# can_skin.net
KiCad netlist of a schematic drawn in EAGLE
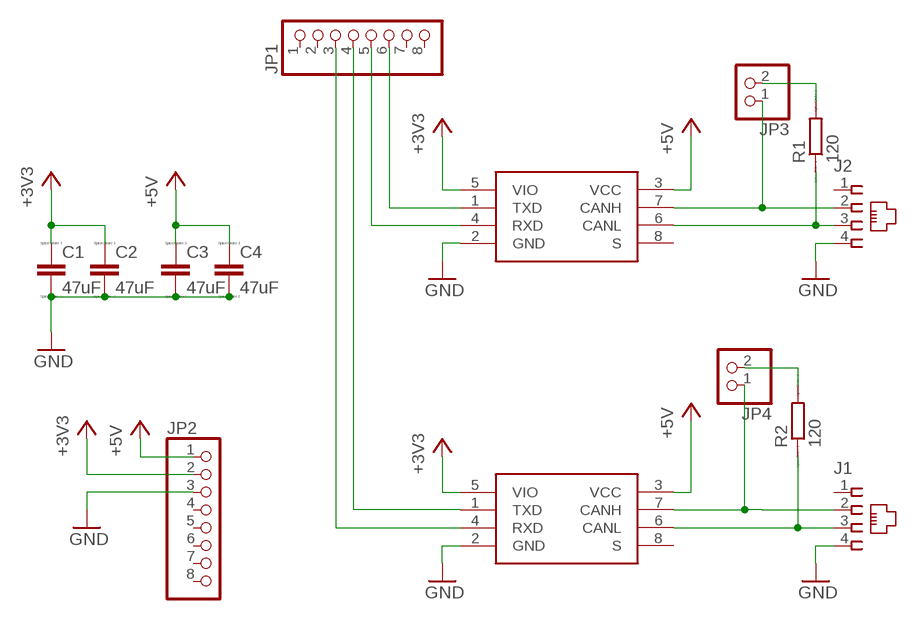
[diagram p0: schematic, sheet 1]

(export (version "E")
  (design (tool "Eeschema 10.0.6"))
  (components
    (comp (ref "C1")
      (value "47uF")
      (footprint "eagle-import:C3216")
      (libsource (lib "eagle-import") (part "C-EUC3216"))
    )
    (comp (ref "C2")
      (value "47uF")
      (footprint "eagle-import:C3216")
      (libsource (lib "eagle-import") (part "C-EUC3216"))
    )
    (comp (ref "C3")
      (value "47uF")
      (footprint "eagle-import:C3216")
      (libsource (lib "eagle-import") (part "C-EUC3216"))
    )
    (comp (ref "C4")
      (value "47uF")
      (footprint "eagle-import:C3216")
      (libsource (lib "eagle-import") (part "C-EUC3216"))
    )
    (comp (ref "J1")
      (value "215875-3")
      (footprint "eagle-import:215875-3")
      (libsource (lib "eagle-import") (part "215875-3"))
    )
    (comp (ref "J2")
      (value "215875-3")
      (footprint "eagle-import:215875-3")
      (libsource (lib "eagle-import") (part "215875-3"))
    )
    (comp (ref "JP1")
      (value "PINHD-1X8")
      (footprint "eagle-import:1X08")
      (libsource (lib "eagle-import") (part "PINHD-1X8"))
    )
    (comp (ref "JP2")
      (value "PINHD-1X8")
      (footprint "eagle-import:1X08")
      (libsource (lib "eagle-import") (part "PINHD-1X8"))
    )
    (comp (ref "JP3")
      (value "PINHD-1X2")
      (footprint "eagle-import:1X02")
      (libsource (lib "eagle-import") (part "PINHD-1X2"))
    )
    (comp (ref "JP4")
      (value "PINHD-1X2")
      (footprint "eagle-import:1X02")
      (libsource (lib "eagle-import") (part "PINHD-1X2"))
    )
    (comp (ref "R1")
      (value "120")
      (footprint "eagle-import:M3216")
      (libsource (lib "eagle-import") (part "R-EU_M3216"))
    )
    (comp (ref "R2")
      (value "120")
      (footprint "eagle-import:M3216")
      (libsource (lib "eagle-import") (part "R-EU_M3216"))
    )
    (comp (ref "U1")
      (value "TJA1051T/3")
      (footprint "eagle-import:SOIC127P600X175-8N")
      (libsource (lib "eagle-import") (part "TJA1051T/3"))
    )
    (comp (ref "U2")
      (value "TJA1051T/3")
      (footprint "eagle-import:SOIC127P600X175-8N")
      (libsource (lib "eagle-import") (part "TJA1051T/3"))
    )
  )
  (nets
    (net (code "1") (name "+3V3") (class "Default")
      (node (ref "C1") (pin "1") (pinfunction "1_1") (pintype "passive"))
      (node (ref "C2") (pin "1") (pinfunction "1_1") (pintype "passive"))
      (node (ref "JP2") (pin "2") (pinfunction "2_2") (pintype "passive"))
      (node (ref "U1") (pin "5") (pinfunction "VIO_5") (pintype "bidirectional"))
      (node (ref "U2") (pin "5") (pinfunction "VIO_5") (pintype "bidirectional"))
    )
    (net (code "2") (name "+5V") (class "Default")
      (node (ref "C3") (pin "1") (pinfunction "1_1") (pintype "passive"))
      (node (ref "C4") (pin "1") (pinfunction "1_1") (pintype "passive"))
      (node (ref "JP2") (pin "1") (pinfunction "1_1") (pintype "passive"))
      (node (ref "U1") (pin "3") (pinfunction "VCC_3") (pintype "bidirectional"))
      (node (ref "U2") (pin "3") (pinfunction "VCC_3") (pintype "bidirectional"))
    )
    (net (code "3") (name "GND") (class "Default")
      (node (ref "C1") (pin "2") (pinfunction "2_2") (pintype "passive"))
      (node (ref "C2") (pin "2") (pinfunction "2_2") (pintype "passive"))
      (node (ref "C3") (pin "2") (pinfunction "2_2") (pintype "passive"))
      (node (ref "C4") (pin "2") (pinfunction "2_2") (pintype "passive"))
      (node (ref "J1") (pin "4") (pinfunction "4_4") (pintype "passive"))
      (node (ref "J2") (pin "4") (pinfunction "4_4") (pintype "passive"))
      (node (ref "JP2") (pin "3") (pinfunction "3_3") (pintype "passive"))
      (node (ref "U1") (pin "2") (pinfunction "GND_2") (pintype "bidirectional"))
      (node (ref "U2") (pin "2") (pinfunction "GND_2") (pintype "bidirectional"))
    )
    (net (code "4") (name "Net-(JP3-Pad2)") (class "Default")
      (node (ref "JP3") (pin "2") (pinfunction "2_2") (pintype "passive"))
      (node (ref "R1") (pin "2") (pinfunction "2_2") (pintype "passive"))
    )
    (net (code "5") (name "Net-(JP4-Pad2)") (class "Default")
      (node (ref "JP4") (pin "2") (pinfunction "2_2") (pintype "passive"))
      (node (ref "R2") (pin "2") (pinfunction "2_2") (pintype "passive"))
    )
    (net (code "6") (name "Net-(U1-CANH)") (class "Default")
      (node (ref "J1") (pin "2") (pinfunction "2_2") (pintype "passive"))
      (node (ref "JP4") (pin "1") (pinfunction "1_1") (pintype "passive"))
      (node (ref "U1") (pin "7") (pinfunction "CANH_7") (pintype "bidirectional"))
    )
    (net (code "7") (name "Net-(U1-CANL)") (class "Default")
      (node (ref "J1") (pin "3") (pinfunction "3_3") (pintype "passive"))
      (node (ref "R2") (pin "1") (pinfunction "1_1") (pintype "passive"))
      (node (ref "U1") (pin "6") (pinfunction "CANL_6") (pintype "bidirectional"))
    )
    (net (code "8") (name "Net-(U1-RXD)") (class "Default")
      (node (ref "JP1") (pin "3") (pinfunction "3_3") (pintype "passive"))
      (node (ref "U1") (pin "4") (pinfunction "RXD_4") (pintype "bidirectional"))
    )
    (net (code "9") (name "Net-(U1-TXD)") (class "Default")
      (node (ref "JP1") (pin "4") (pinfunction "4_4") (pintype "passive"))
      (node (ref "U1") (pin "1") (pinfunction "TXD_1") (pintype "bidirectional"))
    )
    (net (code "10") (name "Net-(U2-CANH)") (class "Default")
      (node (ref "J2") (pin "2") (pinfunction "2_2") (pintype "passive"))
      (node (ref "JP3") (pin "1") (pinfunction "1_1") (pintype "passive"))
      (node (ref "U2") (pin "7") (pinfunction "CANH_7") (pintype "bidirectional"))
    )
    (net (code "11") (name "Net-(U2-CANL)") (class "Default")
      (node (ref "J2") (pin "3") (pinfunction "3_3") (pintype "passive"))
      (node (ref "R1") (pin "1") (pinfunction "1_1") (pintype "passive"))
      (node (ref "U2") (pin "6") (pinfunction "CANL_6") (pintype "bidirectional"))
    )
    (net (code "12") (name "Net-(U2-RXD)") (class "Default")
      (node (ref "JP1") (pin "5") (pinfunction "5_5") (pintype "passive"))
      (node (ref "U2") (pin "4") (pinfunction "RXD_4") (pintype "bidirectional"))
    )
    (net (code "13") (name "Net-(U2-TXD)") (class "Default")
      (node (ref "JP1") (pin "6") (pinfunction "6_6") (pintype "passive"))
      (node (ref "U2") (pin "1") (pinfunction "TXD_1") (pintype "bidirectional"))
    )
    (net (code "14") (name "unconnected-(J1-Pad1)") (class "Default")
      (node (ref "J1") (pin "1") (pinfunction "1_1") (pintype "passive"))
    )
    (net (code "15") (name "unconnected-(J2-Pad1)") (class "Default")
      (node (ref "J2") (pin "1") (pinfunction "1_1") (pintype "passive"))
    )
    (net (code "16") (name "unconnected-(JP1-Pad1)") (class "Default")
      (node (ref "JP1") (pin "1") (pinfunction "1_1") (pintype "passive"))
    )
    (net (code "17") (name "unconnected-(JP1-Pad2)") (class "Default")
      (node (ref "JP1") (pin "2") (pinfunction "2_2") (pintype "passive"))
    )
    (net (code "18") (name "unconnected-(JP1-Pad7)") (class "Default")
      (node (ref "JP1") (pin "7") (pinfunction "7_7") (pintype "passive"))
    )
    (net (code "19") (name "unconnected-(JP1-Pad8)") (class "Default")
      (node (ref "JP1") (pin "8") (pinfunction "8_8") (pintype "passive"))
    )
    (net (code "20") (name "unconnected-(JP2-Pad4)") (class "Default")
      (node (ref "JP2") (pin "4") (pinfunction "4_4") (pintype "passive"))
    )
    (net (code "21") (name "unconnected-(JP2-Pad5)") (class "Default")
      (node (ref "JP2") (pin "5") (pinfunction "5_5") (pintype "passive"))
    )
    (net (code "22") (name "unconnected-(JP2-Pad6)") (class "Default")
      (node (ref "JP2") (pin "6") (pinfunction "6_6") (pintype "passive"))
    )
    (net (code "23") (name "unconnected-(JP2-Pad7)") (class "Default")
      (node (ref "JP2") (pin "7") (pinfunction "7_7") (pintype "passive"))
    )
    (net (code "24") (name "unconnected-(JP2-Pad8)") (class "Default")
      (node (ref "JP2") (pin "8") (pinfunction "8_8") (pintype "passive"))
    )
    (net (code "25") (name "unconnected-(U1-S-Pad8)") (class "Default")
      (node (ref "U1") (pin "8") (pinfunction "S_8") (pintype "bidirectional"))
    )
    (net (code "26") (name "unconnected-(U2-S-Pad8)") (class "Default")
      (node (ref "U2") (pin "8") (pinfunction "S_8") (pintype "bidirectional"))
    )
  )
)
